# jlink-ob.net
KiCad netlist of a schematic drawn in EAGLE
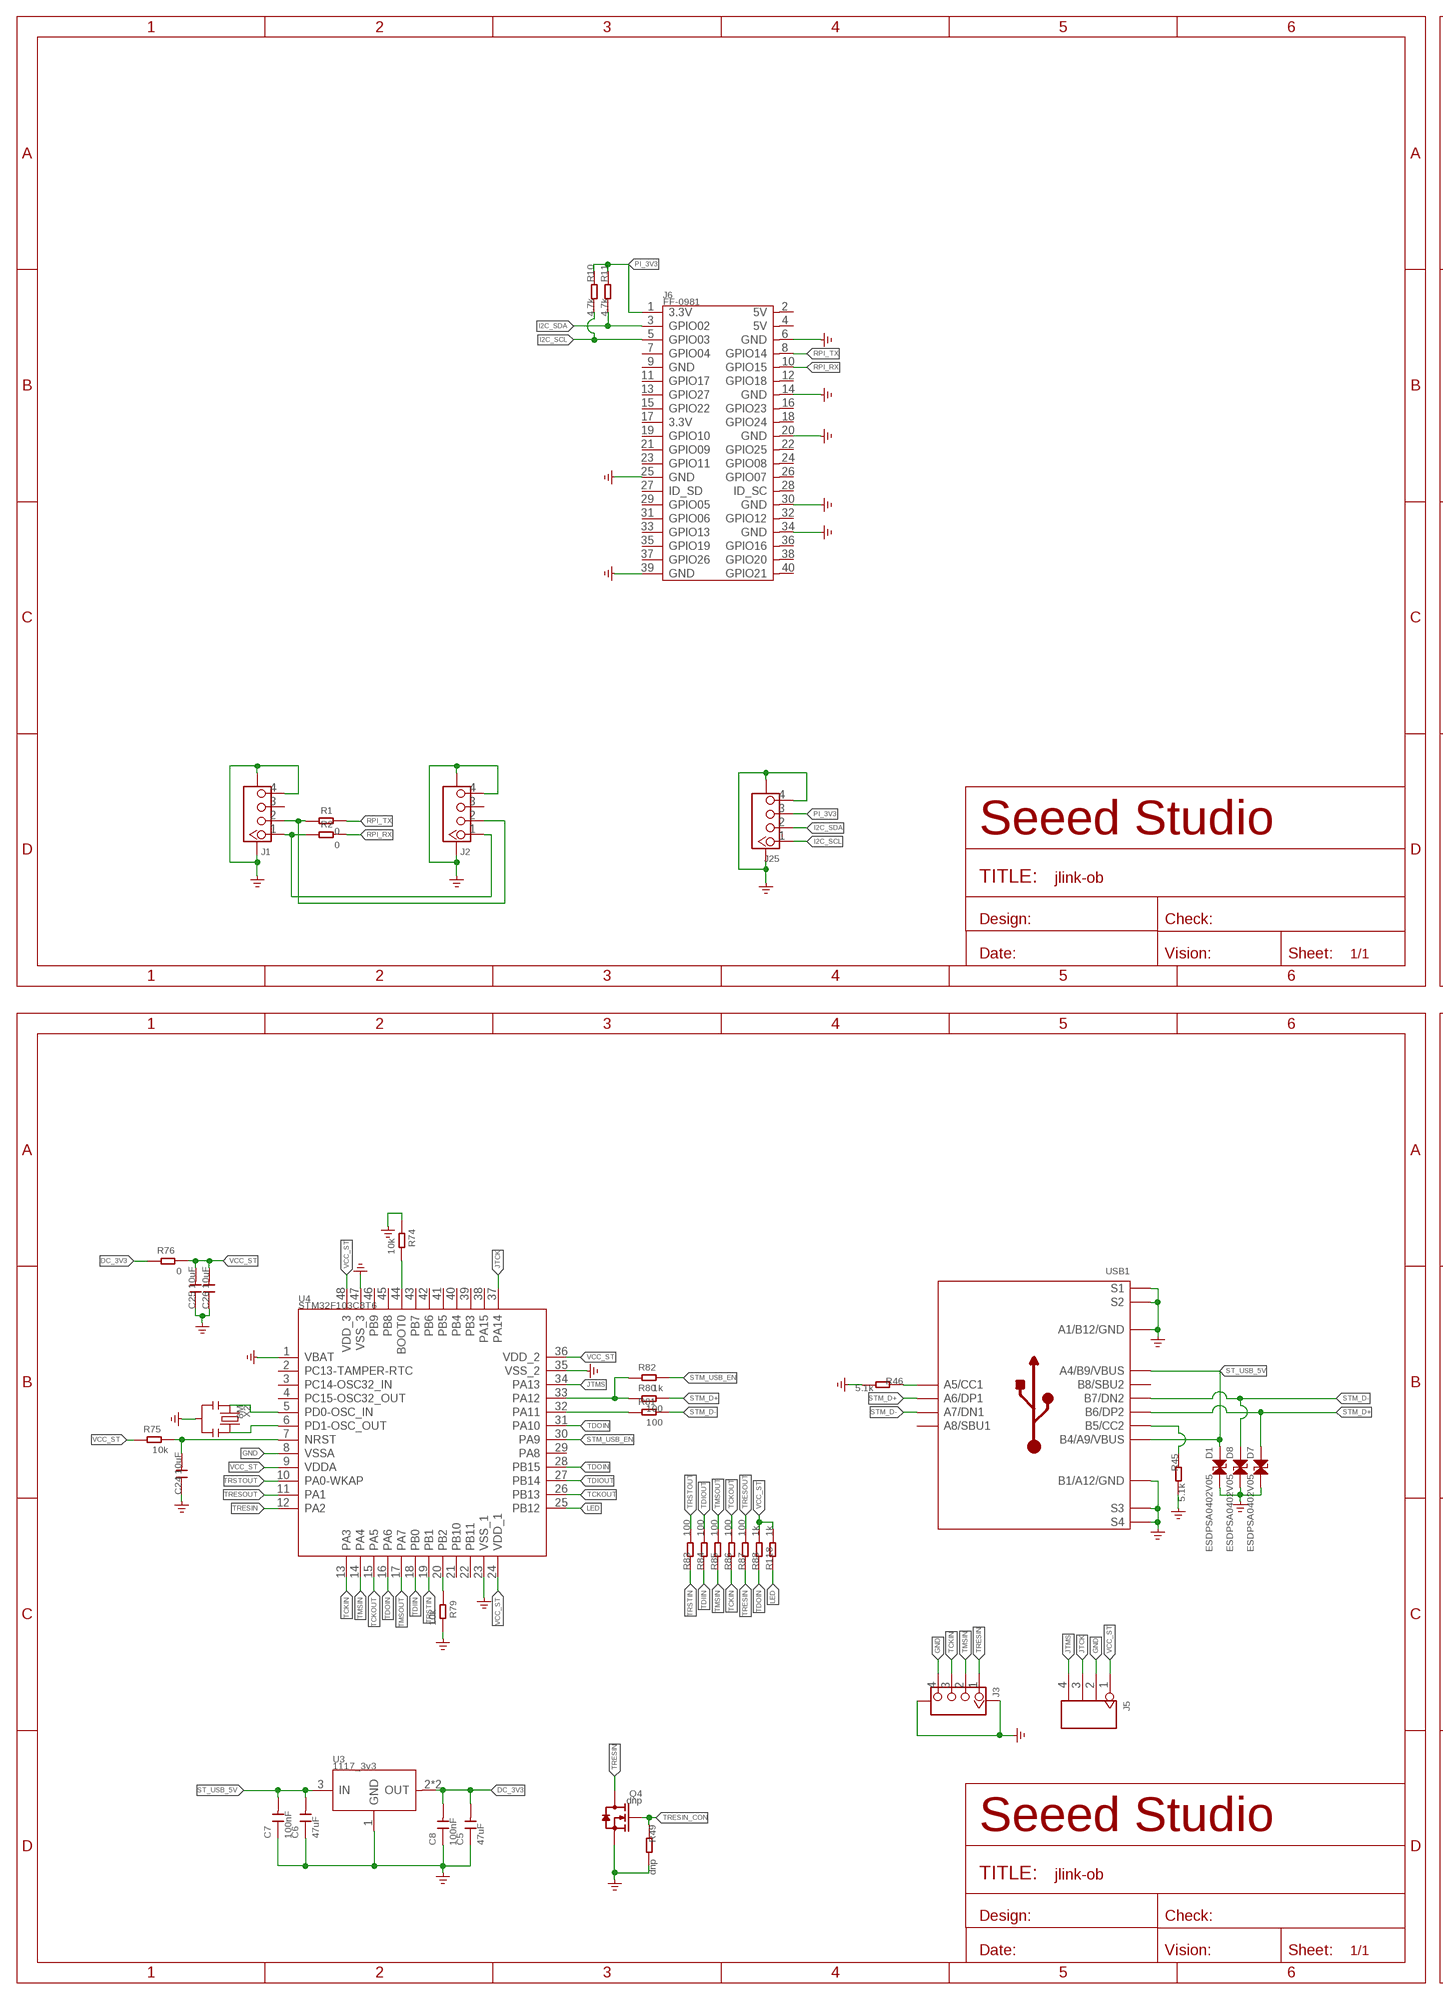
[diagram p0: schematic, sheet 1, part 1 of 2]
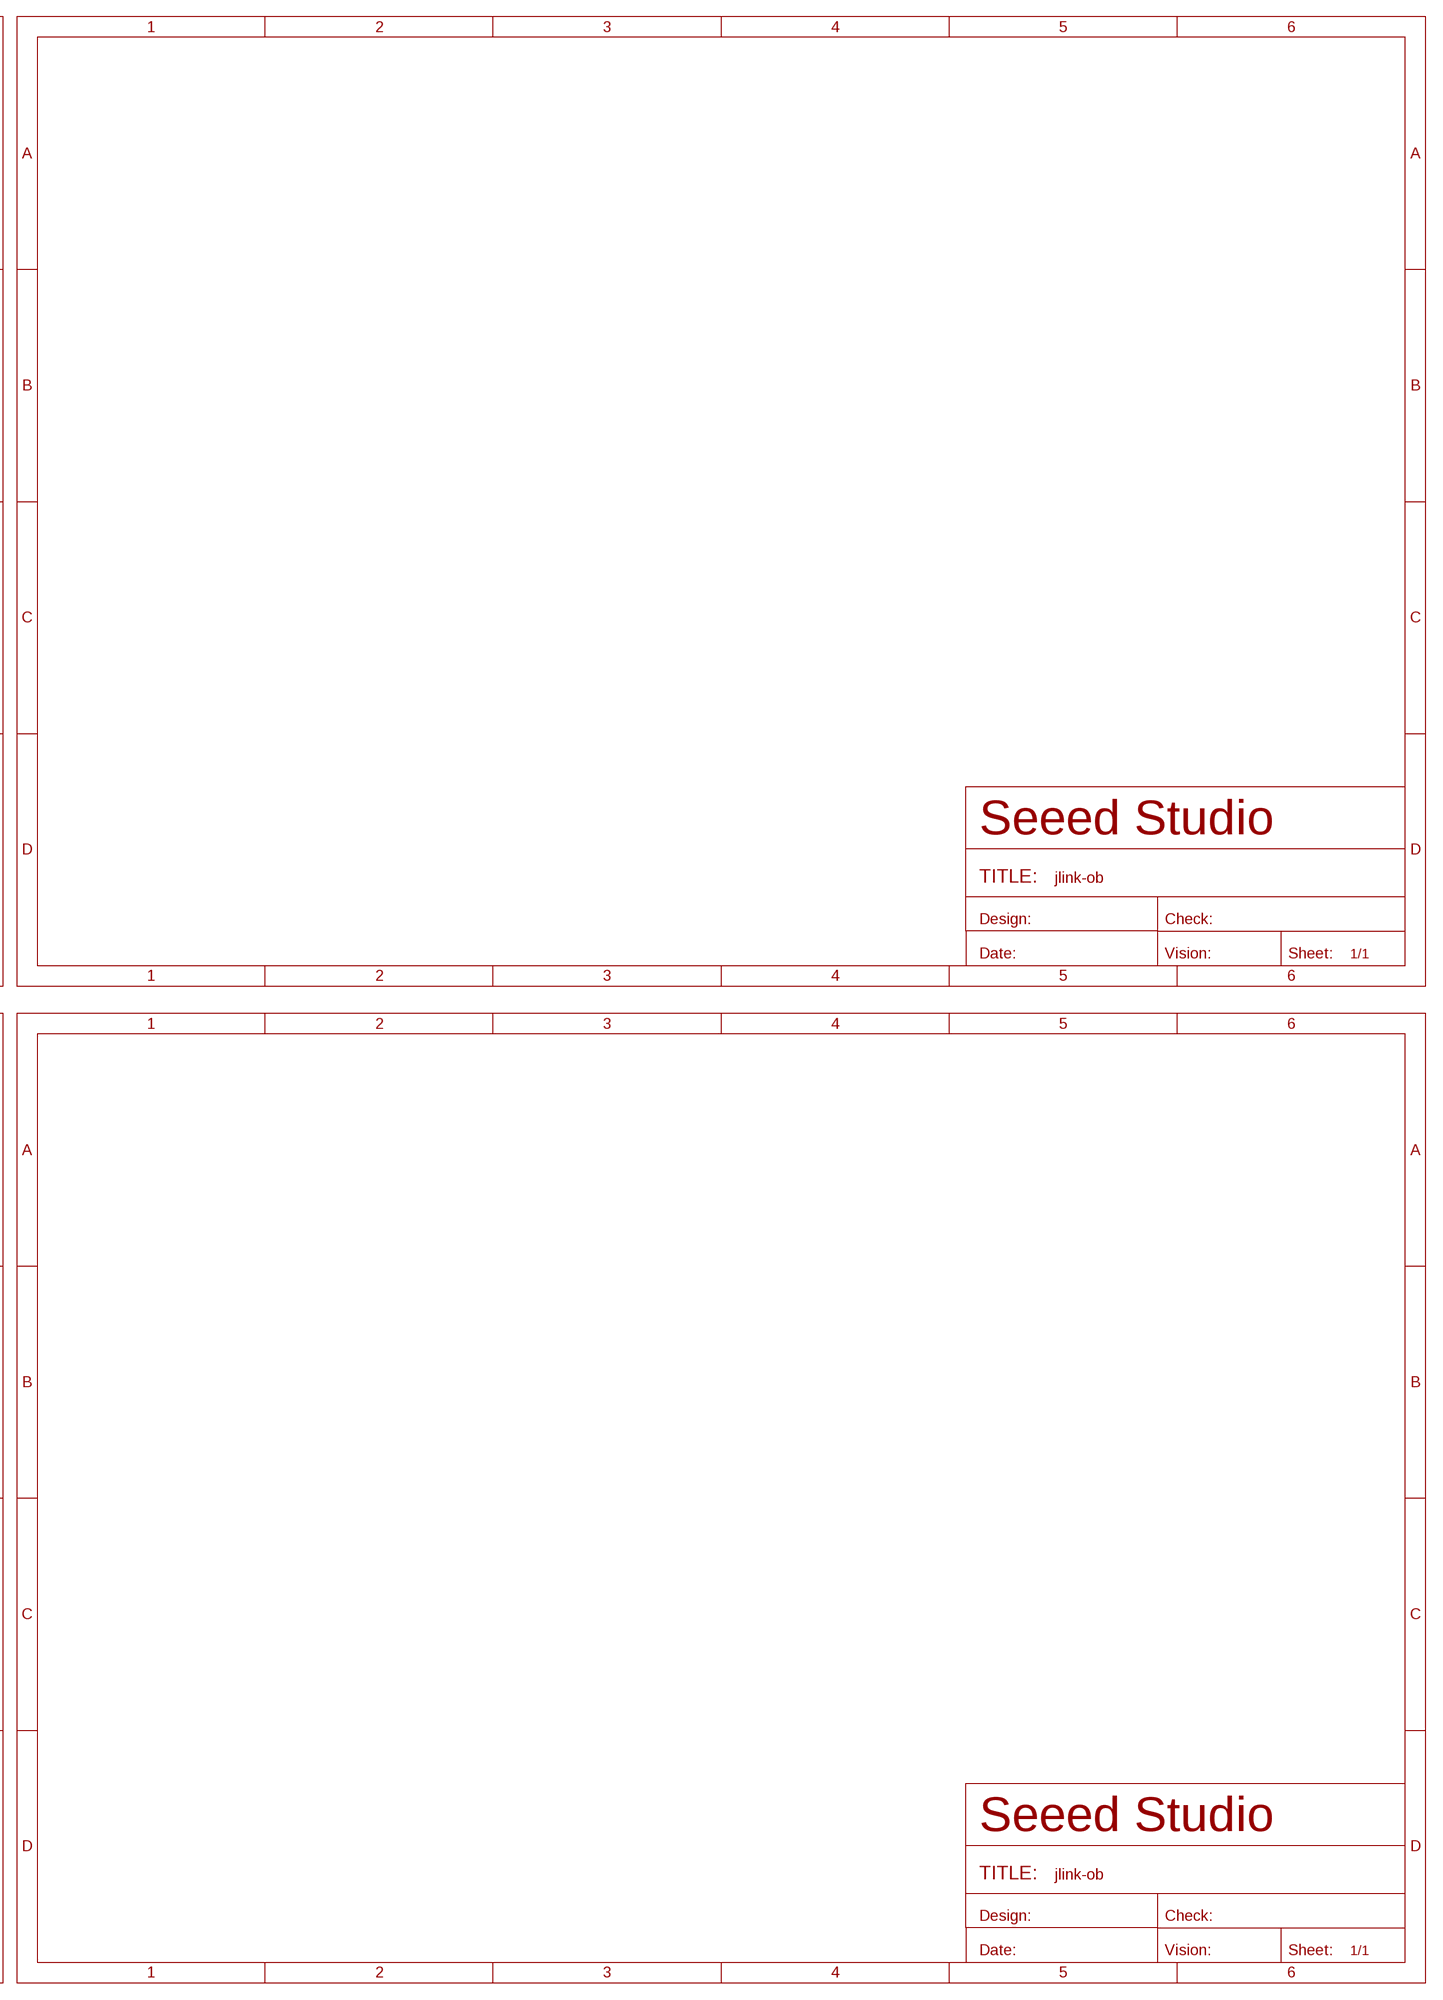
[diagram p1: schematic, sheet 1, part 2 of 2]

(export (version "E")
  (design (tool "Eeschema 10.0.6"))
  (components
    (comp (ref "C5")
      (value "47uF")
      (footprint "eagle-import:C1206")
      (libsource (lib "eagle-import") (part "CAP-1206"))
    )
    (comp (ref "C6")
      (value "47uF")
      (footprint "eagle-import:C1206")
      (libsource (lib "eagle-import") (part "CAP-1206"))
    )
    (comp (ref "C7")
      (value "100nF")
      (footprint "eagle-import:C0603")
      (libsource (lib "eagle-import") (part "CAP-0603"))
    )
    (comp (ref "C8")
      (value "100nF")
      (footprint "eagle-import:C0603")
      (libsource (lib "eagle-import") (part "CAP-0603"))
    )
    (comp (ref "C24")
      (value "10uF")
      (footprint "eagle-import:C0603")
      (libsource (lib "eagle-import") (part "C-0603"))
    )
    (comp (ref "C25")
      (value "10uF")
      (footprint "eagle-import:C0603")
      (libsource (lib "eagle-import") (part "C-0603"))
    )
    (comp (ref "C26")
      (value "10uF")
      (footprint "eagle-import:C0603")
      (libsource (lib "eagle-import") (part "C-0603"))
    )
    (comp (ref "D1")
      (value "ESDPSA0402V05")
      (footprint "eagle-import:ESD-0402")
      (libsource (lib "eagle-import") (part "D-ESD-2P-DOUBLE-0402"))
    )
    (comp (ref "D7")
      (value "ESDPSA0402V05")
      (footprint "eagle-import:ESD-0402")
      (libsource (lib "eagle-import") (part "D-ESD-2P-DOUBLE-0402"))
    )
    (comp (ref "D8")
      (value "ESDPSA0402V05")
      (footprint "eagle-import:ESD-0402")
      (libsource (lib "eagle-import") (part "D-ESD-2P-DOUBLE-0402"))
    )
    (comp (ref "J1")
      (value "GROVE-CONNECTOR-SMD-320110032")
      (footprint "eagle-import:HW4-SMD-2.0-90D")
      (libsource (lib "eagle-import") (part "GROVE-CONNECTOR-SMD-320110032"))
    )
    (comp (ref "J2")
      (value "GROVE-CONNECTOR-SMD-320110032")
      (footprint "eagle-import:HW4-SMD-2.0-90D")
      (libsource (lib "eagle-import") (part "GROVE-CONNECTOR-SMD-320110032"))
    )
    (comp (ref "J3")
      (value "GROVE-CONNECTOR-SMD-320110032")
      (footprint "eagle-import:HW4-SMD-2.0-90D")
      (libsource (lib "eagle-import") (part "GROVE-CONNECTOR-SMD-320110032"))
    )
    (comp (ref "J5")
      (value "HEADER-4P-65/35MIL")
      (footprint "eagle-import:H4-2.54-65_35MIL")
      (libsource (lib "eagle-import") (part "HEADER-4P-65/35MIL"))
    )
    (comp (ref "J6")
      (value "FF-0981")
      (footprint "eagle-import:H2X20-2.54")
      (libsource (lib "eagle-import") (part "HEADER-2X20P"))
    )
    (comp (ref "J25")
      (value "GROVE-CONNECTOR-SMD-320110032")
      (footprint "eagle-import:HW4-SMD-2.0-90D")
      (libsource (lib "eagle-import") (part "GROVE-CONNECTOR-SMD-320110032"))
    )
    (comp (ref "Q4")
      (value "dnp")
      (footprint "eagle-import:SOT-23")
      (libsource (lib "eagle-import") (part "MOSFET-N-SOT23"))
    )
    (comp (ref "R1")
      (value "0")
      (footprint "eagle-import:R0603")
      (libsource (lib "eagle-import") (part "R-0603"))
    )
    (comp (ref "R2")
      (value "0")
      (footprint "eagle-import:R0603")
      (libsource (lib "eagle-import") (part "R-0603"))
    )
    (comp (ref "R10")
      (value "4.7k")
      (footprint "eagle-import:R0603")
      (libsource (lib "eagle-import") (part "RES-0603"))
    )
    (comp (ref "R11")
      (value "4.7k")
      (footprint "eagle-import:R0603")
      (libsource (lib "eagle-import") (part "RES-0603"))
    )
    (comp (ref "R45")
      (value "5.1k")
      (footprint "eagle-import:R0603")
      (libsource (lib "eagle-import") (part "RES-0603"))
    )
    (comp (ref "R46")
      (value "5.1k")
      (footprint "eagle-import:R0603")
      (libsource (lib "eagle-import") (part "RES-0603"))
    )
    (comp (ref "R49")
      (value "dnp")
      (footprint "eagle-import:R0603")
      (libsource (lib "eagle-import") (part "R-0603"))
    )
    (comp (ref "R74")
      (value "10k")
      (footprint "eagle-import:R0603")
      (libsource (lib "eagle-import") (part "R-0603"))
    )
    (comp (ref "R75")
      (value "10k")
      (footprint "eagle-import:R0603")
      (libsource (lib "eagle-import") (part "R-0603"))
    )
    (comp (ref "R76")
      (value "0")
      (footprint "eagle-import:R0603")
      (libsource (lib "eagle-import") (part "R-0603"))
    )
    (comp (ref "R79")
      (value "10k")
      (footprint "eagle-import:R0603")
      (libsource (lib "eagle-import") (part "R-0603"))
    )
    (comp (ref "R80")
      (value "100")
      (footprint "eagle-import:R0603")
      (libsource (lib "eagle-import") (part "R-0603"))
    )
    (comp (ref "R81")
      (value "100")
      (footprint "eagle-import:R0603")
      (libsource (lib "eagle-import") (part "R-0603"))
    )
    (comp (ref "R82")
      (value "1k")
      (footprint "eagle-import:R0603")
      (libsource (lib "eagle-import") (part "R-0603"))
    )
    (comp (ref "R83")
      (value "100")
      (footprint "eagle-import:R0603")
      (libsource (lib "eagle-import") (part "R-0603"))
    )
    (comp (ref "R84")
      (value "100")
      (footprint "eagle-import:R0603")
      (libsource (lib "eagle-import") (part "R-0603"))
    )
    (comp (ref "R85")
      (value "100")
      (footprint "eagle-import:R0603")
      (libsource (lib "eagle-import") (part "R-0603"))
    )
    (comp (ref "R86")
      (value "100")
      (footprint "eagle-import:R0603")
      (libsource (lib "eagle-import") (part "R-0603"))
    )
    (comp (ref "R87")
      (value "100")
      (footprint "eagle-import:R0603")
      (libsource (lib "eagle-import") (part "R-0603"))
    )
    (comp (ref "R88")
      (value "1k")
      (footprint "eagle-import:R0603")
      (libsource (lib "eagle-import") (part "R-0603"))
    )
    (comp (ref "R118")
      (value "1k")
      (footprint "eagle-import:R0603")
      (libsource (lib "eagle-import") (part "R-0603"))
    )
    (comp (ref "U3")
      (value "1117_3v3")
      (footprint "eagle-import:SOT-223")
      (libsource (lib "eagle-import") (part "PMIC-CJ1117S"))
    )
    (comp (ref "U4")
      (value "STM32F103C8T6")
      (footprint "eagle-import:LQFP48")
      (libsource (lib "eagle-import") (part "MCU-STM32F103CBT6-310010004"))
    )
    (comp (ref "USB1")
      (value "USB2.0-TYPE-C-320010698")
      (footprint "eagle-import:USB2.0-TYPE-C")
      (libsource (lib "eagle-import") (part "USB2.0-TYPE-C-320010698"))
    )
    (comp (ref "X2")
      (value "8M")
      (footprint "eagle-import:RESONATOR3-SMD-3.6X1.3X0.8MM")
      (libsource (lib "eagle-import") (part "CRYSTAL-RESONATOR"))
    )
  )
  (nets
    (net (code "1") (name "DC_3V3") (class "Default")
      (node (ref "C5") (pin "2") (pinfunction "2_2") (pintype "passive"))
      (node (ref "C8") (pin "2") (pinfunction "2_2") (pintype "passive"))
      (node (ref "R76") (pin "2") (pinfunction "2_2") (pintype "passive"))
      (node (ref "U3") (pin "2") (pinfunction "OUT_2") (pintype "bidirectional"))
      (node (ref "U3") (pin "TER") (pinfunction "OUT_TER") (pintype "bidirectional"))
    )
    (net (code "2") (name "GND") (class "Default")
      (node (ref "C24") (pin "1") (pinfunction "1_1") (pintype "passive"))
      (node (ref "C25") (pin "1") (pinfunction "1_1") (pintype "passive"))
      (node (ref "C26") (pin "1") (pinfunction "1_1") (pintype "passive"))
      (node (ref "C5") (pin "1") (pinfunction "1_1") (pintype "passive"))
      (node (ref "C6") (pin "1") (pinfunction "1_1") (pintype "passive"))
      (node (ref "C7") (pin "1") (pinfunction "1_1") (pintype "passive"))
      (node (ref "C8") (pin "1") (pinfunction "1_1") (pintype "passive"))
      (node (ref "D1") (pin "2") (pinfunction "2_2") (pintype "bidirectional"))
      (node (ref "D7") (pin "2") (pinfunction "2_2") (pintype "bidirectional"))
      (node (ref "D8") (pin "2") (pinfunction "2_2") (pintype "bidirectional"))
      (node (ref "J1") (pin "4") (pinfunction "4_4") (pintype "bidirectional"))
      (node (ref "J1") (pin "SS1") (pinfunction "SS1_SS1") (pintype "bidirectional"))
      (node (ref "J1") (pin "SS2") (pinfunction "SS2_SS2") (pintype "bidirectional"))
      (node (ref "J2") (pin "4") (pinfunction "4_4") (pintype "bidirectional"))
      (node (ref "J2") (pin "SS1") (pinfunction "SS1_SS1") (pintype "bidirectional"))
      (node (ref "J2") (pin "SS2") (pinfunction "SS2_SS2") (pintype "bidirectional"))
      (node (ref "J25") (pin "4") (pinfunction "4_4") (pintype "bidirectional"))
      (node (ref "J25") (pin "SS1") (pinfunction "SS1_SS1") (pintype "bidirectional"))
      (node (ref "J25") (pin "SS2") (pinfunction "SS2_SS2") (pintype "bidirectional"))
      (node (ref "J3") (pin "4") (pinfunction "4_4") (pintype "bidirectional"))
      (node (ref "J3") (pin "SS1") (pinfunction "SS1_SS1") (pintype "bidirectional"))
      (node (ref "J3") (pin "SS2") (pinfunction "SS2_SS2") (pintype "bidirectional"))
      (node (ref "J5") (pin "2") (pinfunction "P$2_2") (pintype "bidirectional"))
      (node (ref "J6") (pin "14") (pinfunction "GND_14") (pintype "bidirectional"))
      (node (ref "J6") (pin "20") (pinfunction "GND_20") (pintype "bidirectional"))
      (node (ref "J6") (pin "25") (pinfunction "GND_25") (pintype "bidirectional"))
      (node (ref "J6") (pin "30") (pinfunction "GND_30") (pintype "bidirectional"))
      (node (ref "J6") (pin "34") (pinfunction "GND_34") (pintype "bidirectional"))
      (node (ref "J6") (pin "39") (pinfunction "GND_39") (pintype "bidirectional"))
      (node (ref "J6") (pin "6") (pinfunction "GND_6") (pintype "bidirectional"))
      (node (ref "Q4") (pin "2") (pinfunction "S_2") (pintype "passive"))
      (node (ref "R45") (pin "2") (pinfunction "2_2") (pintype "passive"))
      (node (ref "R46") (pin "2") (pinfunction "2_2") (pintype "passive"))
      (node (ref "R49") (pin "2") (pinfunction "2_2") (pintype "passive"))
      (node (ref "R74") (pin "2") (pinfunction "2_2") (pintype "passive"))
      (node (ref "R79") (pin "1") (pinfunction "1_1") (pintype "passive"))
      (node (ref "U3") (pin "1") (pinfunction "GND_1") (pintype "bidirectional"))
      (node (ref "U4") (pin "1") (pinfunction "VBAT_1") (pintype "bidirectional"))
      (node (ref "U4") (pin "23") (pinfunction "VSS_1_23") (pintype "bidirectional"))
      (node (ref "U4") (pin "35") (pinfunction "VSS_2_35") (pintype "bidirectional"))
      (node (ref "U4") (pin "47") (pinfunction "VSS_3_47") (pintype "bidirectional"))
      (node (ref "U4") (pin "8") (pinfunction "VSSA_8") (pintype "bidirectional"))
      (node (ref "USB1") (pin "A1_B12") (pinfunction "A1/B12/GND_A1_B12") (pintype "bidirectional"))
      (node (ref "USB1") (pin "B1_A12") (pinfunction "B1/A12/GND_B1_A12") (pintype "bidirectional"))
      (node (ref "USB1") (pin "S1") (pinfunction "S1_S1") (pintype "bidirectional"))
      (node (ref "USB1") (pin "S2") (pinfunction "S2_S2") (pintype "bidirectional"))
      (node (ref "USB1") (pin "S3") (pinfunction "S3_S3") (pintype "bidirectional"))
      (node (ref "USB1") (pin "S4") (pinfunction "S4_S4") (pintype "bidirectional"))
      (node (ref "USB1") (pin "S5") (pinfunction "S1_S5") (pintype "bidirectional"))
      (node (ref "USB1") (pin "S6") (pinfunction "S2_S6") (pintype "bidirectional"))
      (node (ref "X2") (pin "2") (pinfunction "2_2") (pintype "passive"))
    )
    (net (code "3") (name "I2C_SCL") (class "Default")
      (node (ref "J25") (pin "1") (pinfunction "1_1") (pintype "bidirectional"))
      (node (ref "J6") (pin "5") (pinfunction "GPIO03_5") (pintype "bidirectional"))
      (node (ref "R10") (pin "1") (pinfunction "1_1") (pintype "passive"))
    )
    (net (code "4") (name "I2C_SDA") (class "Default")
      (node (ref "J25") (pin "2") (pinfunction "2_2") (pintype "bidirectional"))
      (node (ref "J6") (pin "3") (pinfunction "GPIO02_3") (pintype "bidirectional"))
      (node (ref "R11") (pin "1") (pinfunction "1_1") (pintype "passive"))
    )
    (net (code "5") (name "JTCK") (class "Default")
      (node (ref "J5") (pin "3") (pinfunction "P$3_3") (pintype "bidirectional"))
      (node (ref "U4") (pin "37") (pinfunction "PA14_37") (pintype "bidirectional"))
    )
    (net (code "6") (name "JTMS") (class "Default")
      (node (ref "J5") (pin "4") (pinfunction "P$4_4") (pintype "bidirectional"))
      (node (ref "U4") (pin "34") (pinfunction "PA13_34") (pintype "bidirectional"))
    )
    (net (code "7") (name "LED") (class "Default")
      (node (ref "R118") (pin "1") (pinfunction "1_1") (pintype "passive"))
      (node (ref "U4") (pin "25") (pinfunction "PB12_25") (pintype "bidirectional"))
    )
    (net (code "8") (name "Net-(J1-Pad1)") (class "Default")
      (node (ref "J1") (pin "1") (pinfunction "1_1") (pintype "bidirectional"))
      (node (ref "J2") (pin "1") (pinfunction "1_1") (pintype "bidirectional"))
      (node (ref "R2") (pin "2") (pinfunction "2_2") (pintype "passive"))
    )
    (net (code "9") (name "Net-(J1-Pad2)") (class "Default")
      (node (ref "J1") (pin "2") (pinfunction "2_2") (pintype "bidirectional"))
      (node (ref "J2") (pin "2") (pinfunction "2_2") (pintype "bidirectional"))
      (node (ref "R1") (pin "2") (pinfunction "2_2") (pintype "passive"))
    )
    (net (code "10") (name "Net-(U4-BOOT0)") (class "Default")
      (node (ref "R74") (pin "1") (pinfunction "1_1") (pintype "passive"))
      (node (ref "U4") (pin "44") (pinfunction "BOOT0_44") (pintype "bidirectional"))
    )
    (net (code "11") (name "Net-(U4-NRST)") (class "Default")
      (node (ref "C24") (pin "2") (pinfunction "2_2") (pintype "passive"))
      (node (ref "R75") (pin "1") (pinfunction "1_1") (pintype "passive"))
      (node (ref "U4") (pin "7") (pinfunction "NRST_7") (pintype "bidirectional"))
    )
    (net (code "12") (name "Net-(U4-PA11)") (class "Default")
      (node (ref "R81") (pin "2") (pinfunction "2_2") (pintype "passive"))
      (node (ref "U4") (pin "32") (pinfunction "PA11_32") (pintype "bidirectional"))
    )
    (net (code "13") (name "Net-(U4-PA12)") (class "Default")
      (node (ref "R80") (pin "2") (pinfunction "2_2") (pintype "passive"))
      (node (ref "R82") (pin "2") (pinfunction "2_2") (pintype "passive"))
      (node (ref "U4") (pin "33") (pinfunction "PA12_33") (pintype "bidirectional"))
    )
    (net (code "14") (name "Net-(U4-PB2)") (class "Default")
      (node (ref "R79") (pin "2") (pinfunction "2_2") (pintype "passive"))
      (node (ref "U4") (pin "20") (pinfunction "PB2_20") (pintype "bidirectional"))
    )
    (net (code "15") (name "Net-(U4-PD0-OSC_IN)") (class "Default")
      (node (ref "U4") (pin "5") (pinfunction "PD0-OSC_IN_5") (pintype "bidirectional"))
      (node (ref "X2") (pin "1") (pinfunction "1_1") (pintype "passive"))
    )
    (net (code "16") (name "Net-(U4-PD1-OSC_OUT)") (class "Default")
      (node (ref "U4") (pin "6") (pinfunction "PD1-OSC_OUT_6") (pintype "bidirectional"))
      (node (ref "X2") (pin "3") (pinfunction "3_3") (pintype "passive"))
    )
    (net (code "17") (name "Net-(USB1-A5{slash}CC1)") (class "Default")
      (node (ref "R46") (pin "1") (pinfunction "1_1") (pintype "passive"))
      (node (ref "USB1") (pin "A5") (pinfunction "A5/CC1_A5") (pintype "bidirectional"))
    )
    (net (code "18") (name "Net-(USB1-B5{slash}CC2)") (class "Default")
      (node (ref "R45") (pin "1") (pinfunction "1_1") (pintype "passive"))
      (node (ref "USB1") (pin "B5") (pinfunction "B5/CC2_B5") (pintype "bidirectional"))
    )
    (net (code "19") (name "PI_3V3") (class "Default")
      (node (ref "J25") (pin "3") (pinfunction "3_3") (pintype "bidirectional"))
      (node (ref "J6") (pin "1") (pinfunction "3.3V_1") (pintype "bidirectional"))
      (node (ref "R10") (pin "2") (pinfunction "2_2") (pintype "passive"))
      (node (ref "R11") (pin "2") (pinfunction "2_2") (pintype "passive"))
    )
    (net (code "20") (name "RPI_RX") (class "Default")
      (node (ref "J6") (pin "10") (pinfunction "GPIO15_10") (pintype "bidirectional"))
      (node (ref "R2") (pin "1") (pinfunction "1_1") (pintype "passive"))
    )
    (net (code "21") (name "RPI_TX") (class "Default")
      (node (ref "J6") (pin "8") (pinfunction "GPIO14_8") (pintype "bidirectional"))
      (node (ref "R1") (pin "1") (pinfunction "1_1") (pintype "passive"))
    )
    (net (code "22") (name "STM_D+") (class "Default")
      (node (ref "D7") (pin "1") (pinfunction "1_1") (pintype "bidirectional"))
      (node (ref "R80") (pin "1") (pinfunction "1_1") (pintype "passive"))
      (node (ref "USB1") (pin "A6") (pinfunction "A6/DP1_A6") (pintype "bidirectional"))
      (node (ref "USB1") (pin "B6") (pinfunction "B6/DP2_B6") (pintype "bidirectional"))
    )
    (net (code "23") (name "STM_D-") (class "Default")
      (node (ref "D8") (pin "1") (pinfunction "1_1") (pintype "bidirectional"))
      (node (ref "R81") (pin "1") (pinfunction "1_1") (pintype "passive"))
      (node (ref "USB1") (pin "A7") (pinfunction "A7/DN1_A7") (pintype "bidirectional"))
      (node (ref "USB1") (pin "B7") (pinfunction "B7/DN2_B7") (pintype "bidirectional"))
    )
    (net (code "24") (name "STM_USB_EN") (class "Default")
      (node (ref "R82") (pin "1") (pinfunction "1_1") (pintype "passive"))
      (node (ref "U4") (pin "30") (pinfunction "PA9_30") (pintype "bidirectional"))
    )
    (net (code "25") (name "ST_USB_5V") (class "Default")
      (node (ref "C6") (pin "2") (pinfunction "2_2") (pintype "passive"))
      (node (ref "C7") (pin "2") (pinfunction "2_2") (pintype "passive"))
      (node (ref "D1") (pin "1") (pinfunction "1_1") (pintype "bidirectional"))
      (node (ref "U3") (pin "3") (pinfunction "IN_3") (pintype "bidirectional"))
      (node (ref "USB1") (pin "A4_B9") (pinfunction "A4/B9/VBUS_A4_B9") (pintype "bidirectional"))
      (node (ref "USB1") (pin "B4_A9") (pinfunction "B4/A9/VBUS_B4_A9") (pintype "bidirectional"))
    )
    (net (code "26") (name "TCKIN") (class "Default")
      (node (ref "J3") (pin "3") (pinfunction "3_3") (pintype "bidirectional"))
      (node (ref "R86") (pin "1") (pinfunction "1_1") (pintype "passive"))
      (node (ref "U4") (pin "13") (pinfunction "PA3_13") (pintype "bidirectional"))
    )
    (net (code "27") (name "TCKOUT") (class "Default")
      (node (ref "R86") (pin "2") (pinfunction "2_2") (pintype "passive"))
      (node (ref "U4") (pin "15") (pinfunction "PA5_15") (pintype "bidirectional"))
      (node (ref "U4") (pin "26") (pinfunction "PB13_26") (pintype "bidirectional"))
    )
    (net (code "28") (name "TDIIN") (class "Default")
      (node (ref "R84") (pin "1") (pinfunction "1_1") (pintype "passive"))
      (node (ref "U4") (pin "18") (pinfunction "PB0_18") (pintype "bidirectional"))
    )
    (net (code "29") (name "TDIOUT") (class "Default")
      (node (ref "R84") (pin "2") (pinfunction "2_2") (pintype "passive"))
      (node (ref "U4") (pin "27") (pinfunction "PB14_27") (pintype "bidirectional"))
    )
    (net (code "30") (name "TDOIN") (class "Default")
      (node (ref "R88") (pin "1") (pinfunction "1_1") (pintype "passive"))
      (node (ref "U4") (pin "16") (pinfunction "PA6_16") (pintype "bidirectional"))
      (node (ref "U4") (pin "28") (pinfunction "PB15_28") (pintype "bidirectional"))
      (node (ref "U4") (pin "31") (pinfunction "PA10_31") (pintype "bidirectional"))
    )
    (net (code "31") (name "TMSIN") (class "Default")
      (node (ref "J3") (pin "2") (pinfunction "2_2") (pintype "bidirectional"))
      (node (ref "R85") (pin "1") (pinfunction "1_1") (pintype "passive"))
      (node (ref "U4") (pin "14") (pinfunction "PA4_14") (pintype "bidirectional"))
    )
    (net (code "32") (name "TMSOUT") (class "Default")
      (node (ref "R85") (pin "2") (pinfunction "2_2") (pintype "passive"))
      (node (ref "U4") (pin "17") (pinfunction "PA7_17") (pintype "bidirectional"))
    )
    (net (code "33") (name "TRESIN") (class "Default")
      (node (ref "J3") (pin "1") (pinfunction "1_1") (pintype "bidirectional"))
      (node (ref "Q4") (pin "3") (pinfunction "D_3") (pintype "passive"))
      (node (ref "R87") (pin "1") (pinfunction "1_1") (pintype "passive"))
      (node (ref "U4") (pin "12") (pinfunction "PA2_12") (pintype "bidirectional"))
    )
    (net (code "34") (name "TRESIN_CON") (class "Default")
      (node (ref "Q4") (pin "1") (pinfunction "G_1") (pintype "passive"))
      (node (ref "R49") (pin "1") (pinfunction "1_1") (pintype "passive"))
    )
    (net (code "35") (name "TRESOUT") (class "Default")
      (node (ref "R87") (pin "2") (pinfunction "2_2") (pintype "passive"))
      (node (ref "U4") (pin "11") (pinfunction "PA1_11") (pintype "bidirectional"))
    )
    (net (code "36") (name "TRSTIN") (class "Default")
      (node (ref "R83") (pin "1") (pinfunction "1_1") (pintype "passive"))
      (node (ref "U4") (pin "19") (pinfunction "PB1_19") (pintype "bidirectional"))
    )
    (net (code "37") (name "TRSTOUT") (class "Default")
      (node (ref "R83") (pin "2") (pinfunction "2_2") (pintype "passive"))
      (node (ref "U4") (pin "10") (pinfunction "PA0-WKAP_10") (pintype "bidirectional"))
    )
    (net (code "38") (name "VCC_ST") (class "Default")
      (node (ref "C25") (pin "2") (pinfunction "2_2") (pintype "passive"))
      (node (ref "C26") (pin "2") (pinfunction "2_2") (pintype "passive"))
      (node (ref "J5") (pin "1") (pinfunction "P$1_1") (pintype "bidirectional"))
      (node (ref "R118") (pin "2") (pinfunction "2_2") (pintype "passive"))
      (node (ref "R75") (pin "2") (pinfunction "2_2") (pintype "passive"))
      (node (ref "R76") (pin "1") (pinfunction "1_1") (pintype "passive"))
      (node (ref "R88") (pin "2") (pinfunction "2_2") (pintype "passive"))
      (node (ref "U4") (pin "24") (pinfunction "VDD_1_24") (pintype "bidirectional"))
      (node (ref "U4") (pin "36") (pinfunction "VDD_2_36") (pintype "bidirectional"))
      (node (ref "U4") (pin "48") (pinfunction "VDD_3_48") (pintype "bidirectional"))
      (node (ref "U4") (pin "9") (pinfunction "VDDA_9") (pintype "bidirectional"))
    )
    (net (code "39") (name "unconnected-(J1-Pad3)") (class "Default")
      (node (ref "J1") (pin "3") (pinfunction "3_3") (pintype "bidirectional"))
    )
    (net (code "40") (name "unconnected-(J2-Pad3)") (class "Default")
      (node (ref "J2") (pin "3") (pinfunction "3_3") (pintype "bidirectional"))
    )
    (net (code "41") (name "unconnected-(J6-3.3V-Pad17)") (class "Default")
      (node (ref "J6") (pin "17") (pinfunction "3.3V_17") (pintype "bidirectional"))
    )
    (net (code "42") (name "unconnected-(J6-5V-Pad2)") (class "Default")
      (node (ref "J6") (pin "2") (pinfunction "5V_2") (pintype "bidirectional"))
    )
    (net (code "43") (name "unconnected-(J6-5V-Pad4)") (class "Default")
      (node (ref "J6") (pin "4") (pinfunction "5V_4") (pintype "bidirectional"))
    )
    (net (code "44") (name "unconnected-(J6-GND-Pad9)") (class "Default")
      (node (ref "J6") (pin "9") (pinfunction "GND_9") (pintype "bidirectional"))
    )
    (net (code "45") (name "unconnected-(J6-GPIO04-Pad7)") (class "Default")
      (node (ref "J6") (pin "7") (pinfunction "GPIO04_7") (pintype "bidirectional"))
    )
    (net (code "46") (name "unconnected-(J6-GPIO05-Pad29)") (class "Default")
      (node (ref "J6") (pin "29") (pinfunction "GPIO05_29") (pintype "bidirectional"))
    )
    (net (code "47") (name "unconnected-(J6-GPIO06-Pad31)") (class "Default")
      (node (ref "J6") (pin "31") (pinfunction "GPIO06_31") (pintype "bidirectional"))
    )
    (net (code "48") (name "unconnected-(J6-GPIO07-Pad26)") (class "Default")
      (node (ref "J6") (pin "26") (pinfunction "GPIO07_26") (pintype "bidirectional"))
    )
    (net (code "49") (name "unconnected-(J6-GPIO08-Pad24)") (class "Default")
      (node (ref "J6") (pin "24") (pinfunction "GPIO08_24") (pintype "bidirectional"))
    )
    (net (code "50") (name "unconnected-(J6-GPIO09-Pad21)") (class "Default")
      (node (ref "J6") (pin "21") (pinfunction "GPIO09_21") (pintype "bidirectional"))
    )
    (net (code "51") (name "unconnected-(J6-GPIO10-Pad19)") (class "Default")
      (node (ref "J6") (pin "19") (pinfunction "GPIO10_19") (pintype "bidirectional"))
    )
    (net (code "52") (name "unconnected-(J6-GPIO11-Pad23)") (class "Default")
      (node (ref "J6") (pin "23") (pinfunction "GPIO11_23") (pintype "bidirectional"))
    )
    (net (code "53") (name "unconnected-(J6-GPIO12-Pad32)") (class "Default")
      (node (ref "J6") (pin "32") (pinfunction "GPIO12_32") (pintype "bidirectional"))
    )
    (net (code "54") (name "unconnected-(J6-GPIO13-Pad33)") (class "Default")
      (node (ref "J6") (pin "33") (pinfunction "GPIO13_33") (pintype "bidirectional"))
    )
    (net (code "55") (name "unconnected-(J6-GPIO16-Pad36)") (class "Default")
      (node (ref "J6") (pin "36") (pinfunction "GPIO16_36") (pintype "bidirectional"))
    )
    (net (code "56") (name "unconnected-(J6-GPIO17-Pad11)") (class "Default")
      (node (ref "J6") (pin "11") (pinfunction "GPIO17_11") (pintype "bidirectional"))
    )
    (net (code "57") (name "unconnected-(J6-GPIO18-Pad12)") (class "Default")
      (node (ref "J6") (pin "12") (pinfunction "GPIO18_12") (pintype "bidirectional"))
    )
    (net (code "58") (name "unconnected-(J6-GPIO19-Pad35)") (class "Default")
      (node (ref "J6") (pin "35") (pinfunction "GPIO19_35") (pintype "bidirectional"))
    )
    (net (code "59") (name "unconnected-(J6-GPIO20-Pad38)") (class "Default")
      (node (ref "J6") (pin "38") (pinfunction "GPIO20_38") (pintype "bidirectional"))
    )
    (net (code "60") (name "unconnected-(J6-GPIO21-Pad40)") (class "Default")
      (node (ref "J6") (pin "40") (pinfunction "GPIO21_40") (pintype "bidirectional"))
    )
    (net (code "61") (name "unconnected-(J6-GPIO22-Pad15)") (class "Default")
      (node (ref "J6") (pin "15") (pinfunction "GPIO22_15") (pintype "bidirectional"))
    )
    (net (code "62") (name "unconnected-(J6-GPIO23-Pad16)") (class "Default")
      (node (ref "J6") (pin "16") (pinfunction "GPIO23_16") (pintype "bidirectional"))
    )
    (net (code "63") (name "unconnected-(J6-GPIO24-Pad18)") (class "Default")
      (node (ref "J6") (pin "18") (pinfunction "GPIO24_18") (pintype "bidirectional"))
    )
    (net (code "64") (name "unconnected-(J6-GPIO25-Pad22)") (class "Default")
      (node (ref "J6") (pin "22") (pinfunction "GPIO25_22") (pintype "bidirectional"))
    )
    (net (code "65") (name "unconnected-(J6-GPIO26-Pad37)") (class "Default")
      (node (ref "J6") (pin "37") (pinfunction "GPIO26_37") (pintype "bidirectional"))
    )
    (net (code "66") (name "unconnected-(J6-GPIO27-Pad13)") (class "Default")
      (node (ref "J6") (pin "13") (pinfunction "GPIO27_13") (pintype "bidirectional"))
    )
    (net (code "67") (name "unconnected-(J6-ID_SC-Pad28)") (class "Default")
      (node (ref "J6") (pin "28") (pinfunction "ID_SC_28") (pintype "bidirectional"))
    )
    (net (code "68") (name "unconnected-(J6-ID_SD-Pad27)") (class "Default")
      (node (ref "J6") (pin "27") (pinfunction "ID_SD_27") (pintype "bidirectional"))
    )
    (net (code "69") (name "unconnected-(U4-PA8-Pad29)") (class "Default")
      (node (ref "U4") (pin "29") (pinfunction "PA8_29") (pintype "bidirectional"))
    )
    (net (code "70") (name "unconnected-(U4-PA15-Pad38)") (class "Default")
      (node (ref "U4") (pin "38") (pinfunction "PA15_38") (pintype "bidirectional"))
    )
    (net (code "71") (name "unconnected-(U4-PB3-Pad39)") (class "Default")
      (node (ref "U4") (pin "39") (pinfunction "PB3_39") (pintype "bidirectional"))
    )
    (net (code "72") (name "unconnected-(U4-PB4-Pad40)") (class "Default")
      (node (ref "U4") (pin "40") (pinfunction "PB4_40") (pintype "bidirectional"))
    )
    (net (code "73") (name "unconnected-(U4-PB5-Pad41)") (class "Default")
      (node (ref "U4") (pin "41") (pinfunction "PB5_41") (pintype "bidirectional"))
    )
    (net (code "74") (name "unconnected-(U4-PB6-Pad42)") (class "Default")
      (node (ref "U4") (pin "42") (pinfunction "PB6_42") (pintype "bidirectional"))
    )
    (net (code "75") (name "unconnected-(U4-PB7-Pad43)") (class "Default")
      (node (ref "U4") (pin "43") (pinfunction "PB7_43") (pintype "bidirectional"))
    )
    (net (code "76") (name "unconnected-(U4-PB8-Pad45)") (class "Default")
      (node (ref "U4") (pin "45") (pinfunction "PB8_45") (pintype "bidirectional"))
    )
    (net (code "77") (name "unconnected-(U4-PB9-Pad46)") (class "Default")
      (node (ref "U4") (pin "46") (pinfunction "PB9_46") (pintype "bidirectional"))
    )
    (net (code "78") (name "unconnected-(U4-PB10-Pad21)") (class "Default")
      (node (ref "U4") (pin "21") (pinfunction "PB10_21") (pintype "bidirectional"))
    )
    (net (code "79") (name "unconnected-(U4-PB11-Pad22)") (class "Default")
      (node (ref "U4") (pin "22") (pinfunction "PB11_22") (pintype "bidirectional"))
    )
    (net (code "80") (name "unconnected-(U4-PC13-TAMPER-RTC-Pad2)") (class "Default")
      (node (ref "U4") (pin "2") (pinfunction "PC13-TAMPER-RTC_2") (pintype "bidirectional"))
    )
    (net (code "81") (name "unconnected-(U4-PC14-OSC32_IN-Pad3)") (class "Default")
      (node (ref "U4") (pin "3") (pinfunction "PC14-OSC32_IN_3") (pintype "bidirectional"))
    )
    (net (code "82") (name "unconnected-(U4-PC15-OSC32_OUT-Pad4)") (class "Default")
      (node (ref "U4") (pin "4") (pinfunction "PC15-OSC32_OUT_4") (pintype "bidirectional"))
    )
    (net (code "83") (name "unconnected-(USB1-A8{slash}SBU1-PadA8)") (class "Default")
      (node (ref "USB1") (pin "A8") (pinfunction "A8/SBU1_A8") (pintype "bidirectional"))
    )
    (net (code "84") (name "unconnected-(USB1-B8{slash}SBU2-PadB8)") (class "Default")
      (node (ref "USB1") (pin "B8") (pinfunction "B8/SBU2_B8") (pintype "bidirectional"))
    )
  )
)
